# 1channelSimple.net
KiCad netlist of a schematic drawn in EAGLE
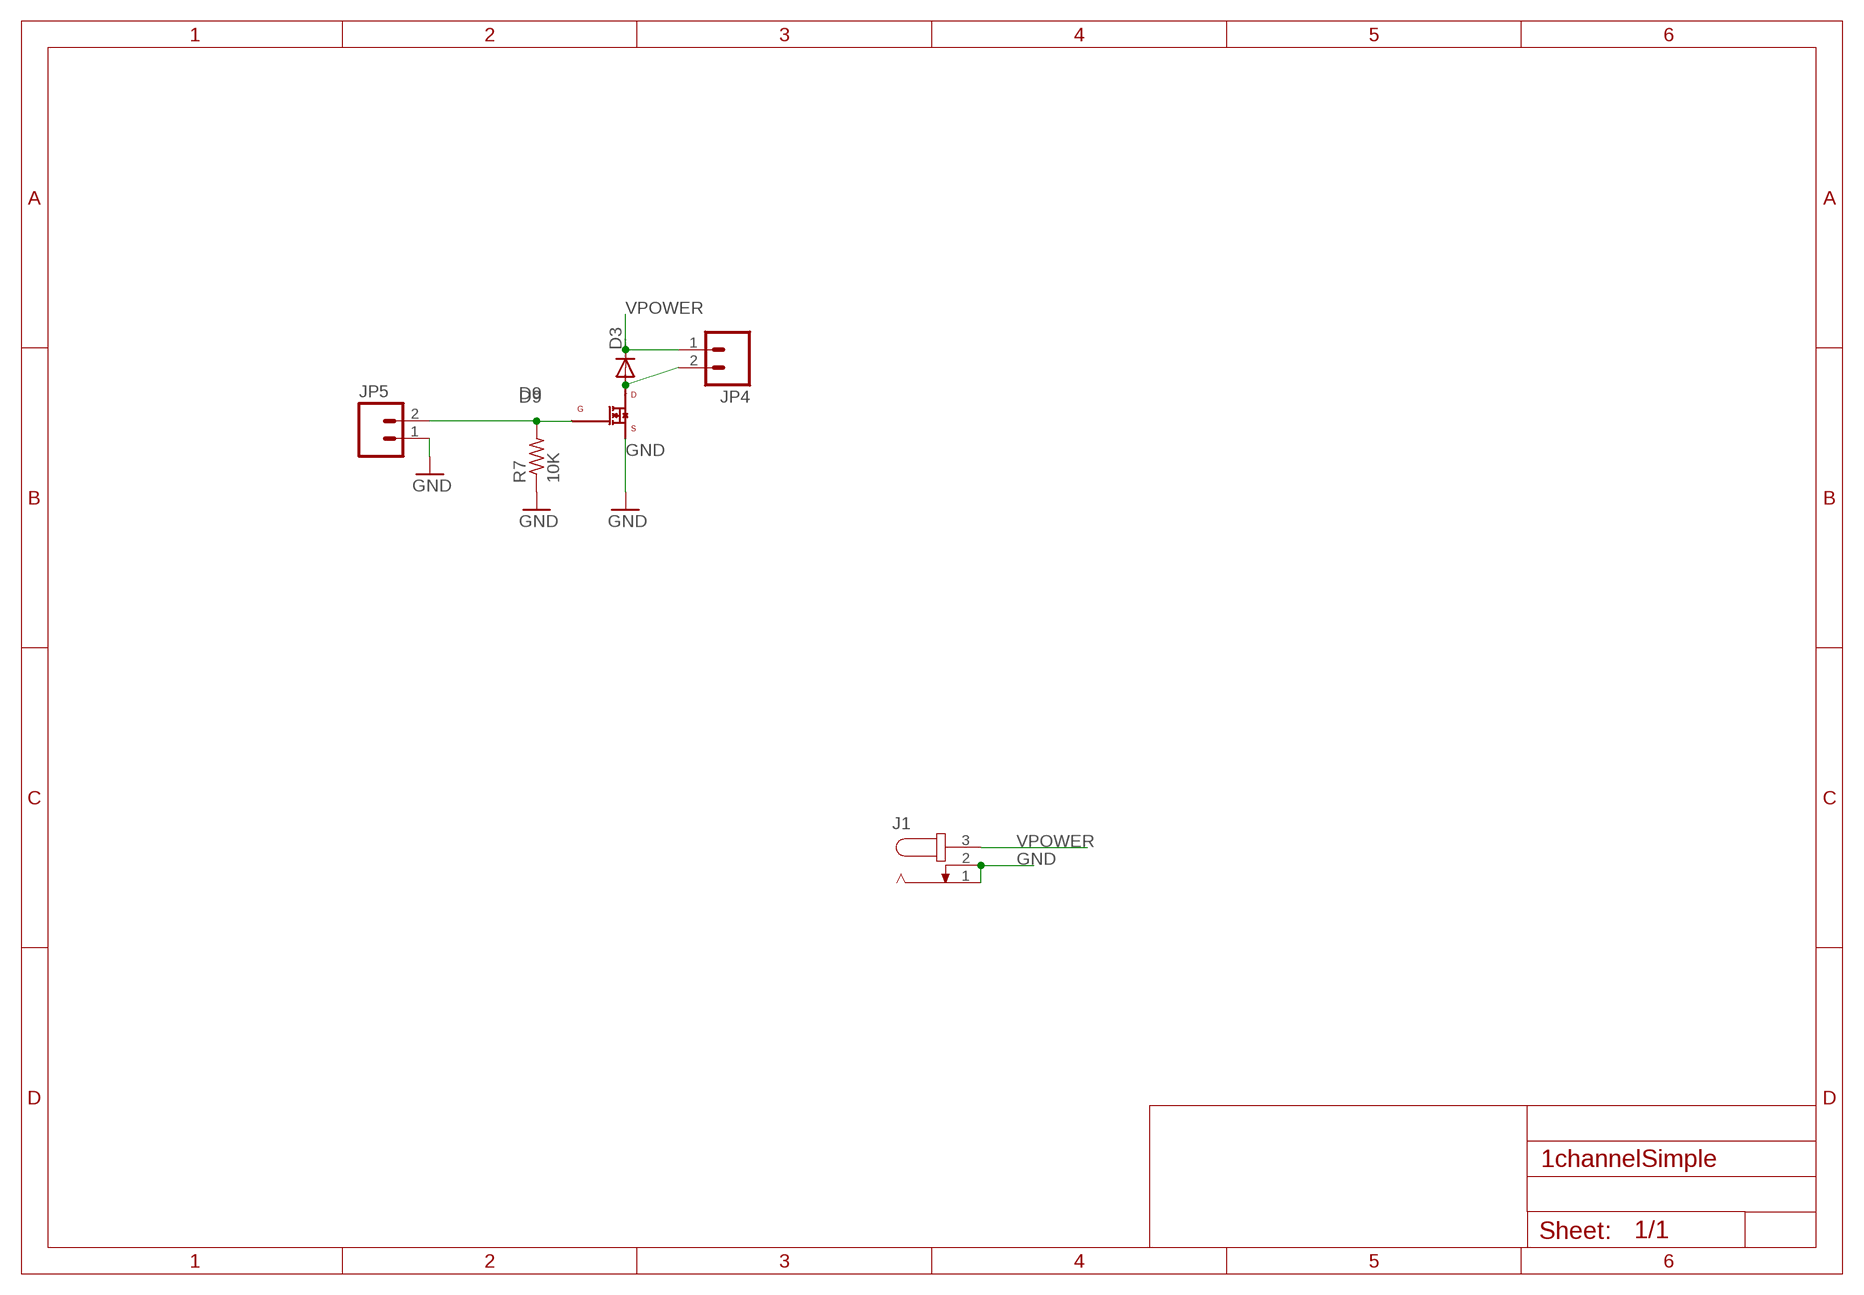
[diagram p0: schematic, sheet 1]

(export (version "E")
  (design (tool "Eeschema 10.0.6"))
  (components
    (comp (ref "D3")
      (value "DIODE-DO-214AC")
      (footprint "eagle-import:DO-214AC")
      (libsource (lib "eagle-import") (part "DIODE-DO-214AC"))
    )
    (comp (ref "J1")
      (value "JACK-PLUG1")
      (footprint "eagle-import:SPC4078")
      (libsource (lib "eagle-import") (part "JACK-PLUG1"))
    )
    (comp (ref "JP4")
      (value "M02PTH")
      (footprint "eagle-import:1X02")
      (libsource (lib "eagle-import") (part "M02PTH"))
    )
    (comp (ref "JP5")
      (value "M02PTH")
      (footprint "eagle-import:1X02")
      (libsource (lib "eagle-import") (part "M02PTH"))
    )
    (comp (ref "Q3")
      (value "IRLML0060")
      (footprint "eagle-import:SOT-23")
      (libsource (lib "eagle-import") (part "IRLML0060"))
    )
    (comp (ref "R7")
      (value "10K")
      (footprint "eagle-import:R0603")
      (libsource (lib "eagle-import") (part "R-US_R0603"))
    )
  )
  (nets
    (net (code "1") (name "/D9") (class "Default")
      (node (ref "JP5") (pin "2") (pinfunction "2_2") (pintype "passive"))
      (node (ref "Q3") (pin "1") (pinfunction "GATE_1") (pintype "bidirectional"))
      (node (ref "R7") (pin "2") (pinfunction "2_2") (pintype "passive"))
    )
    (net (code "2") (name "/VPOWER") (class "Default")
      (node (ref "D3") (pin "C") (pinfunction "C_C") (pintype "passive"))
      (node (ref "J1") (pin "3") (pinfunction "3_3") (pintype "passive"))
      (node (ref "JP4") (pin "1") (pinfunction "1_1") (pintype "passive"))
    )
    (net (code "3") (name "GND") (class "Default")
      (node (ref "J1") (pin "1") (pinfunction "1_1") (pintype "passive"))
      (node (ref "J1") (pin "2") (pinfunction "2_2") (pintype "passive"))
      (node (ref "JP5") (pin "1") (pinfunction "1_1") (pintype "passive"))
      (node (ref "Q3") (pin "2") (pinfunction "SOURCE_2") (pintype "bidirectional"))
      (node (ref "R7") (pin "1") (pinfunction "1_1") (pintype "passive"))
    )
    (net (code "4") (name "Net-(Q3-DRAIN)") (class "Default")
      (node (ref "D3") (pin "A") (pinfunction "A_A") (pintype "passive"))
      (node (ref "JP4") (pin "2") (pinfunction "2_2") (pintype "passive"))
      (node (ref "Q3") (pin "3") (pinfunction "DRAIN_3") (pintype "bidirectional"))
    )
  )
)
